# Power_circuit.net
KiCad netlist of a schematic drawn in Altium Designer
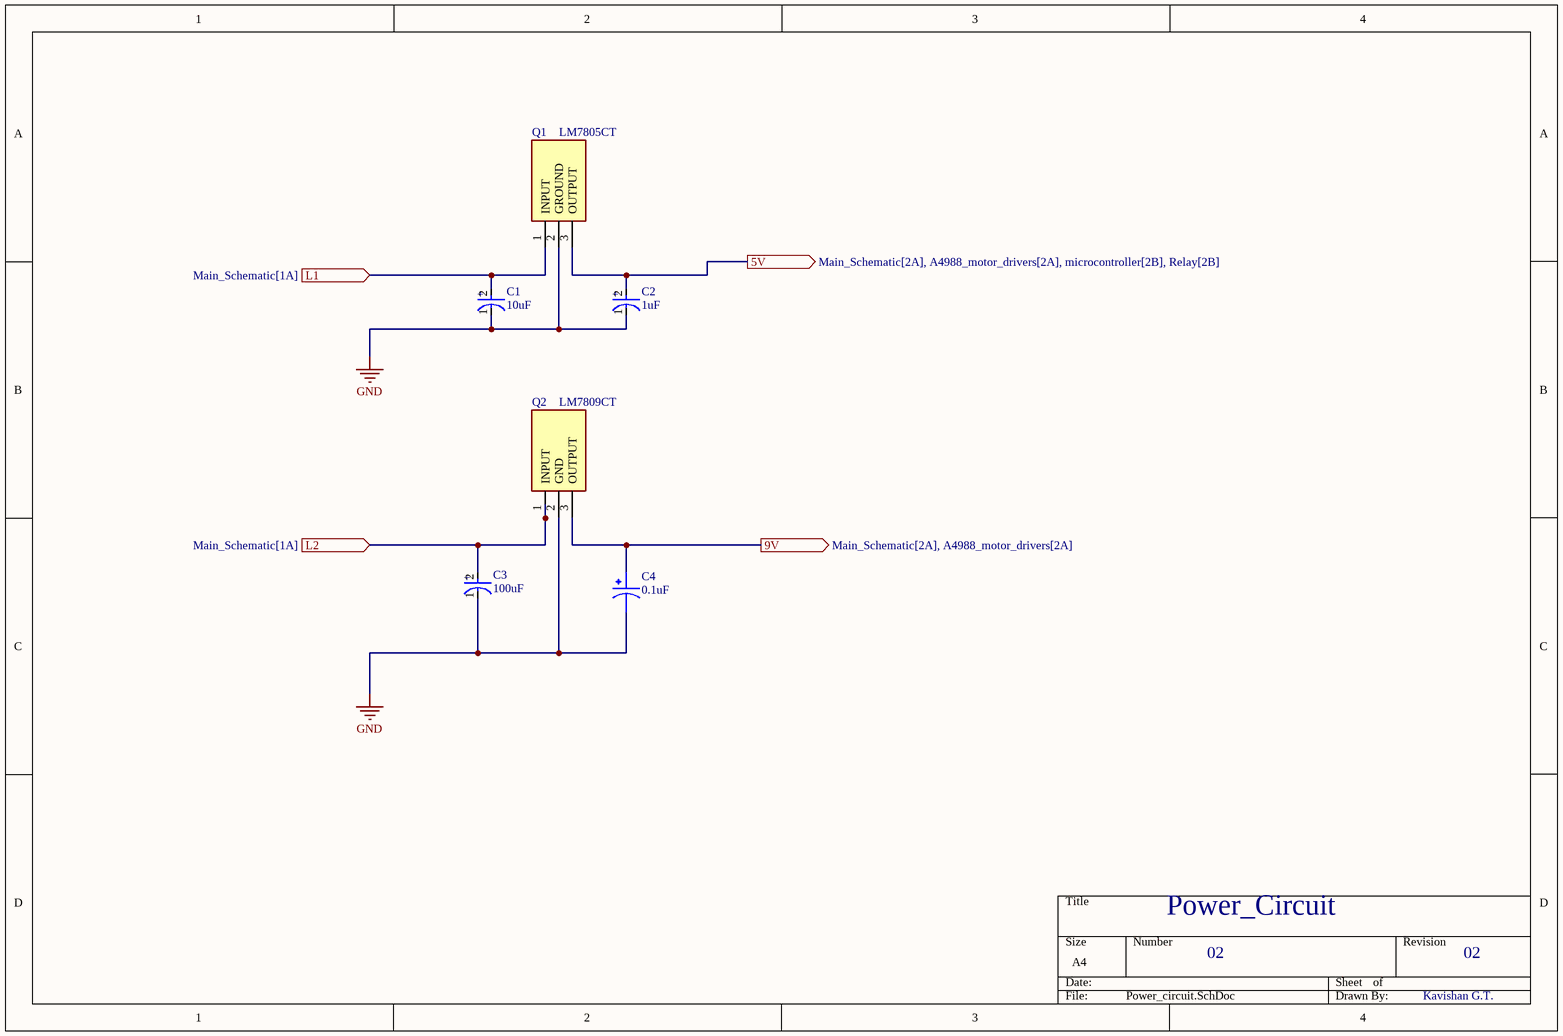
[diagram p0: Power_circuit.SchDoc]

(export (version "E")
  (design (tool "Eeschema 10.0.6"))
  (components
    (comp (ref "C1")
      (value "10uF")
      (footprint "FP-RAD-TH-D_12_5_0_5-L_20-MFG")
      (description "Aluminum Electrolytic Capacitors (Radial Lead Type) 10uF ±20% 450V")
      (fields (field (name "VOLTAGE") "450V") (field (name "TOLERANCE") "20%"))
      (libsource (lib "Altium Content Vault") (part "a00bbbee19879c290e62620ae7e47b1"))
    )
    (comp (ref "C2")
      (value "1uF")
      (footprint "FP-ECA-2CHG010I-MFG")
      (description "CAP ALUM 1UF 20% 160V RADIAL")
      (fields (field (name "TOLERANCE") "20%"))
      (libsource (lib "Altium Content Vault") (part "a00bbbee19879c290e62620ae7e47b1"))
    )
    (comp (ref "C3")
      (value "100uF")
      (footprint "FP-RAD-TH-D_6_3_0_5-L_7_1-MFG")
      (description "Aluminum Electrolytic Capacitors (Radial Lead Type) 100uF ±20% 16V")
      (fields (field (name "VOLTAGE") "16V") (field (name "TOLERANCE") "20%"))
      (libsource (lib "Altium Content Vault") (part "a00bbbee19879c290e62620ae7e47b1"))
    )
    (comp (ref "C4")
      (value "0.1uF")
      (footprint "CAPPRD200W50D550H1250")
      (description "0.1ÂµF 50V Aluminum Electrolytic Capacitors Radial, Can 2000 Hrs @ 85Â°C")
      (fields (field (name "MF") "Nichicon") (field (name "MP") "UVR1H0R1MDD"))
      (libsource (lib "UVR1H0R1MDD") (part "UVR1H0R1MDD"))
    )
    (comp (ref "Q1")
      (value "LM7805CT")
      (footprint "SamacSys:TO254P470X1028X1955-3P")
      (description "Integrated Circuit")
      (fields (field (name "MOUSER PART NUMBER") "926-LM7805CT"))
      (libsource (lib "*") (part "LM7805CT"))
    )
    (comp (ref "Q2")
      (value "LM7809CT")
      (footprint "SamacSys:TO254P470X1016X2019-3P")
      (description "Power Supply")
      (fields (field (name "MOUSER PART NUMBER") "512-LM7809CT"))
      (libsource (lib "*") (part "LM7809CT"))
    )
  )
  (nets
    (net (code "1") (name "/5V") (class "Default")
      (node (ref "C2") (pin "2") (pinfunction "A_2") (pintype "passive"))
      (node (ref "Q1") (pin "3") (pinfunction "OUTPUT_3") (pintype "passive"))
    )
    (net (code "2") (name "/9V") (class "Default")
      (node (ref "C4") (pin "1") (pinfunction "1_1") (pintype "passive"))
      (node (ref "Q2") (pin "3") (pinfunction "OUTPUT_3") (pintype "passive"))
    )
    (net (code "3") (name "/L1") (class "Default")
      (node (ref "C1") (pin "2") (pinfunction "A_2") (pintype "passive"))
      (node (ref "Q1") (pin "1") (pinfunction "INPUT_1") (pintype "passive"))
    )
    (net (code "4") (name "/L2") (class "Default")
      (node (ref "C3") (pin "2") (pinfunction "A_2") (pintype "passive"))
      (node (ref "Q2") (pin "1") (pinfunction "INPUT_1") (pintype "passive"))
    )
    (net (code "5") (name "GND") (class "Default")
      (node (ref "C1") (pin "1") (pinfunction "C_1") (pintype "passive"))
      (node (ref "C2") (pin "1") (pinfunction "C_1") (pintype "passive"))
      (node (ref "C3") (pin "1") (pinfunction "C_1") (pintype "passive"))
      (node (ref "C4") (pin "2") (pinfunction "2_2") (pintype "passive"))
      (node (ref "Q1") (pin "2") (pinfunction "GROUND_2") (pintype "passive"))
      (node (ref "Q2") (pin "2") (pinfunction "GND_2") (pintype "passive"))
    )
  )
)
